# sensor_matrix_03.net
KiCad netlist of a schematic drawn in Altium Designer
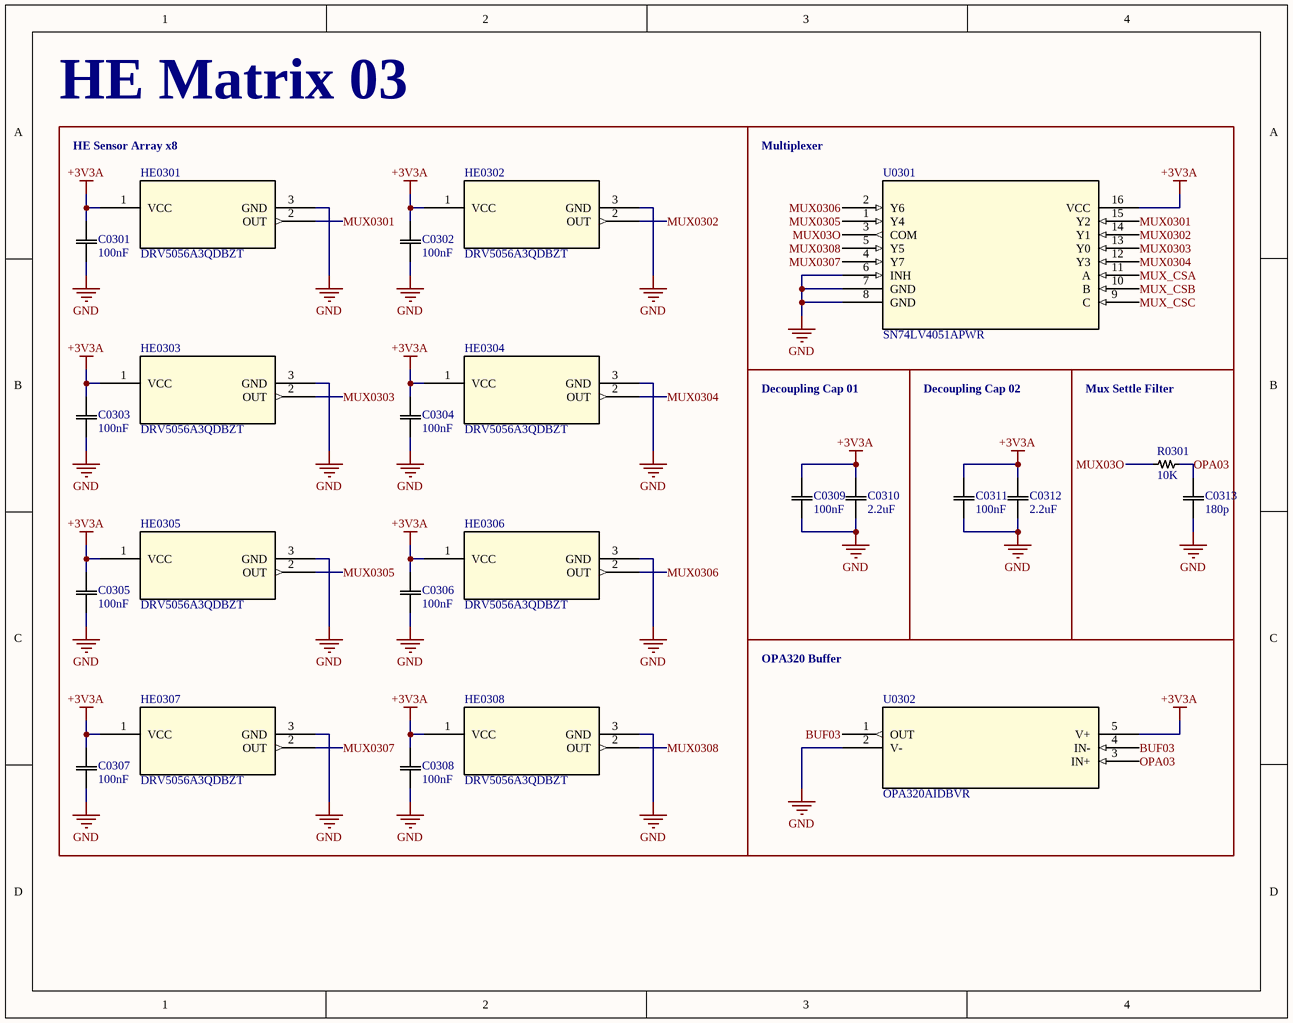
[diagram p0: sensor_matrix_03.SchDoc]

(export (version "E")
  (design (tool "Eeschema 10.0.6"))
  (components
    (comp (ref "C0301")
      (value "100nF")
      (footprint "CAPC10555_55N_KEM")
      (description "SMD Comm X7R, Ceramic, SMD, MLCC, Temperature Stable, 0402")
      (fields
        (field (name "MANUFACTURER_PART_NUMBER") "C0402C104K4RACTU")
        (field (name "COPYRIGHT") "Copyright (C) 2025 Ultra Librarian. All rights reserved.")
      )
      (libsource (lib "SplitHE_Int") (part "C0402"))
    )
    (comp (ref "C0302")
      (value "100nF")
      (footprint "CAPC10555_55N_KEM")
      (description "SMD Comm X7R, Ceramic, SMD, MLCC, Temperature Stable, 0402")
      (fields
        (field (name "MANUFACTURER_PART_NUMBER") "C0402C104K4RACTU")
        (field (name "COPYRIGHT") "Copyright (C) 2025 Ultra Librarian. All rights reserved.")
      )
      (libsource (lib "SplitHE_Int") (part "C0402"))
    )
    (comp (ref "C0303")
      (value "100nF")
      (footprint "CAPC10555_55N_KEM")
      (description "SMD Comm X7R, Ceramic, SMD, MLCC, Temperature Stable, 0402")
      (fields
        (field (name "MANUFACTURER_PART_NUMBER") "C0402C104K4RACTU")
        (field (name "COPYRIGHT") "Copyright (C) 2025 Ultra Librarian. All rights reserved.")
      )
      (libsource (lib "SplitHE_Int") (part "C0402"))
    )
    (comp (ref "C0304")
      (value "100nF")
      (footprint "CAPC10555_55N_KEM")
      (description "SMD Comm X7R, Ceramic, SMD, MLCC, Temperature Stable, 0402")
      (fields
        (field (name "MANUFACTURER_PART_NUMBER") "C0402C104K4RACTU")
        (field (name "COPYRIGHT") "Copyright (C) 2025 Ultra Librarian. All rights reserved.")
      )
      (libsource (lib "SplitHE_Int") (part "C0402"))
    )
    (comp (ref "C0305")
      (value "100nF")
      (footprint "CAPC10555_55N_KEM")
      (description "SMD Comm X7R, Ceramic, SMD, MLCC, Temperature Stable, 0402")
      (fields
        (field (name "MANUFACTURER_PART_NUMBER") "C0402C104K4RACTU")
        (field (name "COPYRIGHT") "Copyright (C) 2025 Ultra Librarian. All rights reserved.")
      )
      (libsource (lib "SplitHE_Int") (part "C0402"))
    )
    (comp (ref "C0306")
      (value "100nF")
      (footprint "CAPC10555_55N_KEM")
      (description "SMD Comm X7R, Ceramic, SMD, MLCC, Temperature Stable, 0402")
      (fields
        (field (name "MANUFACTURER_PART_NUMBER") "C0402C104K4RACTU")
        (field (name "COPYRIGHT") "Copyright (C) 2025 Ultra Librarian. All rights reserved.")
      )
      (libsource (lib "SplitHE_Int") (part "C0402"))
    )
    (comp (ref "C0307")
      (value "100nF")
      (footprint "CAPC10555_55N_KEM")
      (description "SMD Comm X7R, Ceramic, SMD, MLCC, Temperature Stable, 0402")
      (fields
        (field (name "MANUFACTURER_PART_NUMBER") "C0402C104K4RACTU")
        (field (name "COPYRIGHT") "Copyright (C) 2025 Ultra Librarian. All rights reserved.")
      )
      (libsource (lib "SplitHE_Int") (part "C0402"))
    )
    (comp (ref "C0308")
      (value "100nF")
      (footprint "CAPC10555_55N_KEM")
      (description "SMD Comm X7R, Ceramic, SMD, MLCC, Temperature Stable, 0402")
      (fields
        (field (name "MANUFACTURER_PART_NUMBER") "C0402C104K4RACTU")
        (field (name "COPYRIGHT") "Copyright (C) 2025 Ultra Librarian. All rights reserved.")
      )
      (libsource (lib "SplitHE_Int") (part "C0402"))
    )
    (comp (ref "C0309")
      (value "100nF")
      (footprint "CAPC10555_55N_KEM")
      (description "SMD Comm X7R, Ceramic, SMD, MLCC, Temperature Stable, 0402")
      (fields
        (field (name "MANUFACTURER_PART_NUMBER") "C0402C104K4RACTU")
        (field (name "COPYRIGHT") "Copyright (C) 2025 Ultra Librarian. All rights reserved.")
      )
      (libsource (lib "SplitHE_Int") (part "C0402"))
    )
    (comp (ref "C0310")
      (value "2.2uF")
      (footprint "CAPC10555_55N_KEM")
      (description "SMD Comm X7R, Ceramic, SMD, MLCC, Temperature Stable, 0402")
      (fields
        (field (name "MANUFACTURER_PART_NUMBER") "C0402C104K4RACTU")
        (field (name "COPYRIGHT") "Copyright (C) 2025 Ultra Librarian. All rights reserved.")
      )
      (libsource (lib "SplitHE_Int") (part "C0402"))
    )
    (comp (ref "C0311")
      (value "100nF")
      (footprint "CAPC10555_55N_KEM")
      (description "SMD Comm X7R, Ceramic, SMD, MLCC, Temperature Stable, 0402")
      (fields
        (field (name "MANUFACTURER_PART_NUMBER") "C0402C104K4RACTU")
        (field (name "COPYRIGHT") "Copyright (C) 2025 Ultra Librarian. All rights reserved.")
      )
      (libsource (lib "SplitHE_Int") (part "C0402"))
    )
    (comp (ref "C0312")
      (value "2.2uF")
      (footprint "CAPC10555_55N_KEM")
      (description "SMD Comm X7R, Ceramic, SMD, MLCC, Temperature Stable, 0402")
      (fields
        (field (name "MANUFACTURER_PART_NUMBER") "C0402C104K4RACTU")
        (field (name "COPYRIGHT") "Copyright (C) 2025 Ultra Librarian. All rights reserved.")
      )
      (libsource (lib "SplitHE_Int") (part "C0402"))
    )
    (comp (ref "C0313")
      (value "180p")
      (footprint "CAPC10555_55N_KEM")
      (description "SMD Comm X7R, Ceramic, SMD, MLCC, Temperature Stable, 0402")
      (fields
        (field (name "MANUFACTURER_PART_NUMBER") "C0402C104K4RACTU")
        (field (name "COPYRIGHT") "Copyright (C) 2025 Ultra Librarian. All rights reserved.")
      )
      (libsource (lib "SplitHE_Int") (part "C0402"))
    )
    (comp (ref "HE0301")
      (value "DRV5056A3QDBZT")
      (footprint "DBZ3_TEX")
      (description "Ratiometric unipolar linear hall effect sensor with analog output 3-SOT-23 -40 to 125")
      (fields (field (name "COPYRIGHT") "Copyright (C) 2025 Ultra Librarian. All rights reserved."))
      (libsource (lib "DRV5056A3QDBZT") (part "DRV5056A3QDBZT"))
    )
    (comp (ref "HE0302")
      (value "DRV5056A3QDBZT")
      (footprint "DBZ3_TEX")
      (description "Ratiometric unipolar linear hall effect sensor with analog output 3-SOT-23 -40 to 125")
      (fields (field (name "COPYRIGHT") "Copyright (C) 2025 Ultra Librarian. All rights reserved."))
      (libsource (lib "DRV5056A3QDBZT") (part "DRV5056A3QDBZT"))
    )
    (comp (ref "HE0303")
      (value "DRV5056A3QDBZT")
      (footprint "DBZ3_TEX")
      (description "Ratiometric unipolar linear hall effect sensor with analog output 3-SOT-23 -40 to 125")
      (fields (field (name "COPYRIGHT") "Copyright (C) 2025 Ultra Librarian. All rights reserved."))
      (libsource (lib "DRV5056A3QDBZT") (part "DRV5056A3QDBZT"))
    )
    (comp (ref "HE0304")
      (value "DRV5056A3QDBZT")
      (footprint "DBZ3_TEX")
      (description "Ratiometric unipolar linear hall effect sensor with analog output 3-SOT-23 -40 to 125")
      (fields (field (name "COPYRIGHT") "Copyright (C) 2025 Ultra Librarian. All rights reserved."))
      (libsource (lib "DRV5056A3QDBZT") (part "DRV5056A3QDBZT"))
    )
    (comp (ref "HE0305")
      (value "DRV5056A3QDBZT")
      (footprint "DBZ3_TEX")
      (description "Ratiometric unipolar linear hall effect sensor with analog output 3-SOT-23 -40 to 125")
      (fields (field (name "COPYRIGHT") "Copyright (C) 2025 Ultra Librarian. All rights reserved."))
      (libsource (lib "DRV5056A3QDBZT") (part "DRV5056A3QDBZT"))
    )
    (comp (ref "HE0306")
      (value "DRV5056A3QDBZT")
      (footprint "DBZ3_TEX")
      (description "Ratiometric unipolar linear hall effect sensor with analog output 3-SOT-23 -40 to 125")
      (fields (field (name "COPYRIGHT") "Copyright (C) 2025 Ultra Librarian. All rights reserved."))
      (libsource (lib "DRV5056A3QDBZT") (part "DRV5056A3QDBZT"))
    )
    (comp (ref "HE0307")
      (value "DRV5056A3QDBZT")
      (footprint "DBZ3_TEX")
      (description "Ratiometric unipolar linear hall effect sensor with analog output 3-SOT-23 -40 to 125")
      (fields (field (name "COPYRIGHT") "Copyright (C) 2025 Ultra Librarian. All rights reserved."))
      (libsource (lib "DRV5056A3QDBZT") (part "DRV5056A3QDBZT"))
    )
    (comp (ref "HE0308")
      (value "DRV5056A3QDBZT")
      (footprint "DBZ3_TEX")
      (description "Ratiometric unipolar linear hall effect sensor with analog output 3-SOT-23 -40 to 125")
      (fields (field (name "COPYRIGHT") "Copyright (C) 2025 Ultra Librarian. All rights reserved."))
      (libsource (lib "DRV5056A3QDBZT") (part "DRV5056A3QDBZT"))
    )
    (comp (ref "R0301")
      (value "10K")
      (footprint "RES0402_CPF_TYCO_TYC")
      (description "CPF 0402 RL")
      (fields
        (field (name "MANUFACTURER_PART_NUMBER") "CPF0402B33RE1")
        (field (name "COPYRIGHT") "Copyright (C) 2025 Ultra Librarian. All rights reserved.")
      )
      (libsource (lib "SplitHE_Int") (part "R0402"))
    )
    (comp (ref "U0301")
      (value "SN74LV4051APWR")
      (footprint "PW16")
      (description "5V 8:1 one-channel general-purpose analog multiplexer 16-TSSOP -40 to 85")
      (fields (field (name "COPYRIGHT") "Copyright (C) 2025 Ultra Librarian. All rights reserved."))
      (libsource (lib "SN74LV4051APWR") (part "SN74LV4051APWR"))
    )
    (comp (ref "U0302")
      (value "OPA320AIDBVR")
      (footprint "DBV5")
      (description "Precision, zero-crossover, 20-MHz, 0.9-pA Ib, RRIO, CMOS operational amplifier 5-SOT-23 -40 to 125")
      (fields (field (name "COPYRIGHT") "Copyright (C) 2025 Ultra Librarian. All rights reserved."))
      (libsource (lib "OPA320AIDBVR") (part "OPA320AIDBVR"))
    )
  )
  (nets
    (net (code "1") (name "+3V3A") (class "Default")
      (node (ref "C0301") (pin "2") (pinfunction "2_2") (pintype "passive"))
      (node (ref "C0302") (pin "2") (pinfunction "2_2") (pintype "passive"))
      (node (ref "C0303") (pin "2") (pinfunction "2_2") (pintype "passive"))
      (node (ref "C0304") (pin "2") (pinfunction "2_2") (pintype "passive"))
      (node (ref "C0305") (pin "2") (pinfunction "2_2") (pintype "passive"))
      (node (ref "C0306") (pin "2") (pinfunction "2_2") (pintype "passive"))
      (node (ref "C0307") (pin "2") (pinfunction "2_2") (pintype "passive"))
      (node (ref "C0308") (pin "2") (pinfunction "2_2") (pintype "passive"))
      (node (ref "C0309") (pin "2") (pinfunction "2_2") (pintype "passive"))
      (node (ref "C0310") (pin "2") (pinfunction "2_2") (pintype "passive"))
      (node (ref "C0311") (pin "2") (pinfunction "2_2") (pintype "passive"))
      (node (ref "C0312") (pin "2") (pinfunction "2_2") (pintype "passive"))
      (node (ref "HE0301") (pin "1") (pinfunction "VCC_1") (pintype "power_in"))
      (node (ref "HE0302") (pin "1") (pinfunction "VCC_1") (pintype "power_in"))
      (node (ref "HE0303") (pin "1") (pinfunction "VCC_1") (pintype "power_in"))
      (node (ref "HE0304") (pin "1") (pinfunction "VCC_1") (pintype "power_in"))
      (node (ref "HE0305") (pin "1") (pinfunction "VCC_1") (pintype "power_in"))
      (node (ref "HE0306") (pin "1") (pinfunction "VCC_1") (pintype "power_in"))
      (node (ref "HE0307") (pin "1") (pinfunction "VCC_1") (pintype "power_in"))
      (node (ref "HE0308") (pin "1") (pinfunction "VCC_1") (pintype "power_in"))
      (node (ref "U0301") (pin "16") (pinfunction "VCC_16") (pintype "power_in"))
      (node (ref "U0302") (pin "5") (pinfunction "V+_5") (pintype "power_in"))
    )
    (net (code "2") (name "/BUF03") (class "Default")
      (node (ref "U0302") (pin "1") (pinfunction "OUT_1") (pintype "output"))
      (node (ref "U0302") (pin "4") (pinfunction "IN-_4") (pintype "input"))
    )
    (net (code "3") (name "/MUX03O") (class "Default")
      (node (ref "R0301") (pin "2") (pinfunction "2_2") (pintype "passive"))
      (node (ref "U0301") (pin "3") (pinfunction "COM_3") (pintype "output"))
    )
    (net (code "4") (name "/MUX0301") (class "Default")
      (node (ref "HE0301") (pin "2") (pinfunction "OUT_2") (pintype "output"))
      (node (ref "U0301") (pin "15") (pinfunction "Y2_15") (pintype "input"))
    )
    (net (code "5") (name "/MUX0302") (class "Default")
      (node (ref "HE0302") (pin "2") (pinfunction "OUT_2") (pintype "output"))
      (node (ref "U0301") (pin "14") (pinfunction "Y1_14") (pintype "input"))
    )
    (net (code "6") (name "/MUX0303") (class "Default")
      (node (ref "HE0303") (pin "2") (pinfunction "OUT_2") (pintype "output"))
      (node (ref "U0301") (pin "13") (pinfunction "Y0_13") (pintype "input"))
    )
    (net (code "7") (name "/MUX0304") (class "Default")
      (node (ref "HE0304") (pin "2") (pinfunction "OUT_2") (pintype "output"))
      (node (ref "U0301") (pin "12") (pinfunction "Y3_12") (pintype "input"))
    )
    (net (code "8") (name "/MUX0305") (class "Default")
      (node (ref "HE0305") (pin "2") (pinfunction "OUT_2") (pintype "output"))
      (node (ref "U0301") (pin "1") (pinfunction "Y4_1") (pintype "input"))
    )
    (net (code "9") (name "/MUX0306") (class "Default")
      (node (ref "HE0306") (pin "2") (pinfunction "OUT_2") (pintype "output"))
      (node (ref "U0301") (pin "2") (pinfunction "Y6_2") (pintype "input"))
    )
    (net (code "10") (name "/MUX0307") (class "Default")
      (node (ref "HE0307") (pin "2") (pinfunction "OUT_2") (pintype "output"))
      (node (ref "U0301") (pin "4") (pinfunction "Y7_4") (pintype "input"))
    )
    (net (code "11") (name "/MUX0308") (class "Default")
      (node (ref "HE0308") (pin "2") (pinfunction "OUT_2") (pintype "output"))
      (node (ref "U0301") (pin "5") (pinfunction "Y5_5") (pintype "input"))
    )
    (net (code "12") (name "/MUX_CSA") (class "Default")
      (node (ref "U0301") (pin "11") (pinfunction "A_11") (pintype "input"))
    )
    (net (code "13") (name "/MUX_CSB") (class "Default")
      (node (ref "U0301") (pin "10") (pinfunction "B_10") (pintype "input"))
    )
    (net (code "14") (name "/MUX_CSC") (class "Default")
      (node (ref "U0301") (pin "9") (pinfunction "C_9") (pintype "input"))
    )
    (net (code "15") (name "/OPA03") (class "Default")
      (node (ref "C0313") (pin "2") (pinfunction "2_2") (pintype "passive"))
      (node (ref "R0301") (pin "1") (pinfunction "1_1") (pintype "passive"))
      (node (ref "U0302") (pin "3") (pinfunction "IN+_3") (pintype "input"))
    )
    (net (code "16") (name "GND") (class "Default")
      (node (ref "C0301") (pin "1") (pinfunction "1_1") (pintype "passive"))
      (node (ref "C0302") (pin "1") (pinfunction "1_1") (pintype "passive"))
      (node (ref "C0303") (pin "1") (pinfunction "1_1") (pintype "passive"))
      (node (ref "C0304") (pin "1") (pinfunction "1_1") (pintype "passive"))
      (node (ref "C0305") (pin "1") (pinfunction "1_1") (pintype "passive"))
      (node (ref "C0306") (pin "1") (pinfunction "1_1") (pintype "passive"))
      (node (ref "C0307") (pin "1") (pinfunction "1_1") (pintype "passive"))
      (node (ref "C0308") (pin "1") (pinfunction "1_1") (pintype "passive"))
      (node (ref "C0309") (pin "1") (pinfunction "1_1") (pintype "passive"))
      (node (ref "C0310") (pin "1") (pinfunction "1_1") (pintype "passive"))
      (node (ref "C0311") (pin "1") (pinfunction "1_1") (pintype "passive"))
      (node (ref "C0312") (pin "1") (pinfunction "1_1") (pintype "passive"))
      (node (ref "C0313") (pin "1") (pinfunction "1_1") (pintype "passive"))
      (node (ref "HE0301") (pin "3") (pinfunction "GND_3") (pintype "power_in"))
      (node (ref "HE0302") (pin "3") (pinfunction "GND_3") (pintype "power_in"))
      (node (ref "HE0303") (pin "3") (pinfunction "GND_3") (pintype "power_in"))
      (node (ref "HE0304") (pin "3") (pinfunction "GND_3") (pintype "power_in"))
      (node (ref "HE0305") (pin "3") (pinfunction "GND_3") (pintype "power_in"))
      (node (ref "HE0306") (pin "3") (pinfunction "GND_3") (pintype "power_in"))
      (node (ref "HE0307") (pin "3") (pinfunction "GND_3") (pintype "power_in"))
      (node (ref "HE0308") (pin "3") (pinfunction "GND_3") (pintype "power_in"))
      (node (ref "U0301") (pin "6") (pinfunction "INH_6") (pintype "input"))
      (node (ref "U0301") (pin "7") (pinfunction "GND_7") (pintype "power_in"))
      (node (ref "U0301") (pin "8") (pinfunction "GND_8") (pintype "power_in"))
      (node (ref "U0302") (pin "2") (pinfunction "V-_2") (pintype "power_in"))
    )
  )
)
